# design.net
KiCad netlist of a schematic drawn in Altium Designer
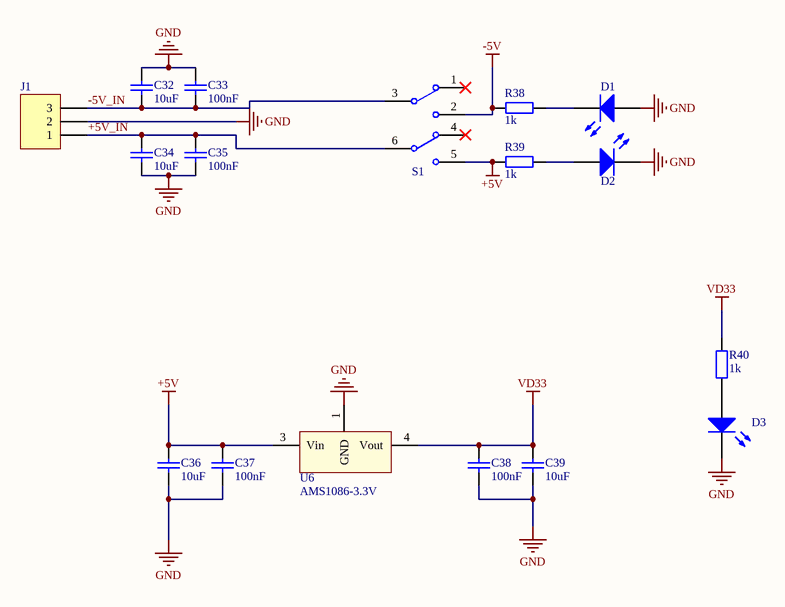
[diagram p0: 电源电路.SchDoc]

(export (version "E")
  (design (tool "Eeschema 10.0.6"))
  (components
    (comp (ref "C32")
      (value "10uF")
      (footprint "LC-0805_C")
      (description "100nF��0805��50V,+/-10%")
      (libsource (lib "ECG") (part "Cap"))
    )
    (comp (ref "C33")
      (value "100nF")
      (footprint "LC-0805_C")
      (description "100nF��0805��50V,+/-10%")
      (libsource (lib "ECG") (part "Cap"))
    )
    (comp (ref "C34")
      (value "10uF")
      (footprint "LC-0805_C")
      (description "100nF��0805��50V,+/-10%")
      (libsource (lib "ECG") (part "Cap"))
    )
    (comp (ref "C35")
      (value "100nF")
      (footprint "LC-0805_C")
      (description "100nF��0805��50V,+/-10%")
      (libsource (lib "ECG") (part "Cap"))
    )
    (comp (ref "C36")
      (value "10uF")
      (footprint "LC-0805_C")
      (description "100nF��0805��50V,+/-10%")
      (libsource (lib "ECG") (part "Cap"))
    )
    (comp (ref "C37")
      (value "100nF")
      (footprint "LC-0805_C")
      (description "100nF��0805��50V,+/-10%")
      (libsource (lib "ECG") (part "Cap"))
    )
    (comp (ref "C38")
      (value "100nF")
      (footprint "LC-0805_C")
      (description "100nF��0805��50V,+/-10%")
      (libsource (lib "ECG") (part "Cap"))
    )
    (comp (ref "C39")
      (value "10uF")
      (footprint "LC-0805_C")
      (description "100nF��0805��50V,+/-10%")
      (libsource (lib "ECG") (part "Cap"))
    )
    (comp (ref "D1")
      (value "LED0")
      (footprint "0805-POLAR")
      (description "��������ܣ�0805���׷��̹�")
      (fields (field (name "PUBLISHER") "Altium Limited"))
      (libsource (lib "ECG") (part "LED0"))
    )
    (comp (ref "D2")
      (value "LED0")
      (footprint "0805-POLAR")
      (description "��������ܣ�0805���׷��̹�")
      (fields (field (name "PUBLISHER") "Altium Limited"))
      (libsource (lib "ECG") (part "LED0"))
    )
    (comp (ref "D3")
      (value "LED0")
      (footprint "0805-POLAR")
      (description "��������ܣ�0805���׷��̹�")
      (fields (field (name "PUBLISHER") "Altium Limited"))
      (libsource (lib "ECG") (part "LED0"))
    )
    (comp (ref "J1")
      (value "������")
      (footprint "HDR1X3")
      (description "1*3Pin,2.54mm��൥����")
      (fields (field (name "PUBLISHER") "Altium Limited"))
      (libsource (lib "ECG") (part "Header 3"))
    )
    (comp (ref "R38")
      (value "1k")
      (footprint "LC-0805_R")
      (description "10k��,0805,��5%")
      (libsource (lib "ECG") (part "R"))
    )
    (comp (ref "R39")
      (value "1k")
      (footprint "LC-0805_R")
      (description "10k��,0805,��5%")
      (libsource (lib "ECG") (part "R"))
    )
    (comp (ref "R40")
      (value "1k")
      (footprint "LC-0805_R")
      (description "10k��,0805,��5%")
      (libsource (lib "ECG") (part "R"))
    )
    (comp (ref "S1")
      (value "��������")
      (footprint "DPDT-6")
      (description "8*8mm����˫·��������")
      (libsource (lib "ECG") (part "SW-6"))
    )
    (comp (ref "U6")
      (value "AMS1086-3.3V")
      (footprint "TO-252")
      (description "AMS1086-3.3V,TO252��װ")
      (libsource (lib "ECG") (part "AMS1086-3.3"))
    )
  )
  (nets
    (net (code "1") (name "+5V") (class "Default")
      (node (ref "C36") (pin "1") (pinfunction "1_1") (pintype "passive"))
      (node (ref "C37") (pin "1") (pinfunction "1_1") (pintype "passive"))
      (node (ref "R39") (pin "1") (pintype "passive"))
      (node (ref "S1") (pin "5") (pinfunction "5_5") (pintype "passive"))
      (node (ref "U6") (pin "3") (pinfunction "Vin_3") (pintype "passive"))
    )
    (net (code "2") (name "-5V") (class "Default")
      (node (ref "R38") (pin "1") (pintype "passive"))
      (node (ref "S1") (pin "2") (pinfunction "2_2") (pintype "passive"))
    )
    (net (code "3") (name "/+5V_IN") (class "Default")
      (node (ref "C34") (pin "1") (pinfunction "1_1") (pintype "passive"))
      (node (ref "C35") (pin "1") (pinfunction "1_1") (pintype "passive"))
      (node (ref "J1") (pin "1") (pinfunction "1_1") (pintype "passive"))
      (node (ref "S1") (pin "6") (pinfunction "6_6") (pintype "passive"))
    )
    (net (code "4") (name "/-5V_IN") (class "Default")
      (node (ref "C32") (pin "2") (pinfunction "2_2") (pintype "passive"))
      (node (ref "C33") (pin "2") (pinfunction "2_2") (pintype "passive"))
      (node (ref "J1") (pin "3") (pinfunction "3_3") (pintype "passive"))
      (node (ref "S1") (pin "3") (pinfunction "3_3") (pintype "passive"))
    )
    (net (code "5") (name "GND") (class "Default")
      (node (ref "C32") (pin "1") (pinfunction "1_1") (pintype "passive"))
      (node (ref "C33") (pin "1") (pinfunction "1_1") (pintype "passive"))
      (node (ref "C34") (pin "2") (pinfunction "2_2") (pintype "passive"))
      (node (ref "C35") (pin "2") (pinfunction "2_2") (pintype "passive"))
      (node (ref "C36") (pin "2") (pinfunction "2_2") (pintype "passive"))
      (node (ref "C37") (pin "2") (pinfunction "2_2") (pintype "passive"))
      (node (ref "C38") (pin "2") (pinfunction "2_2") (pintype "passive"))
      (node (ref "C39") (pin "2") (pinfunction "2_2") (pintype "passive"))
      (node (ref "D1") (pin "1") (pinfunction "A_1") (pintype "passive"))
      (node (ref "D2") (pin "2") (pinfunction "K_2") (pintype "passive"))
      (node (ref "D3") (pin "2") (pinfunction "K_2") (pintype "passive"))
      (node (ref "J1") (pin "2") (pinfunction "2_2") (pintype "passive"))
      (node (ref "U6") (pin "1") (pinfunction "GND_1") (pintype "passive"))
    )
    (net (code "6") (name "Net-(D1-K)") (class "Default")
      (node (ref "D1") (pin "2") (pinfunction "K_2") (pintype "passive"))
      (node (ref "R38") (pin "2") (pintype "passive"))
    )
    (net (code "7") (name "Net-(D2-A)") (class "Default")
      (node (ref "D2") (pin "1") (pinfunction "A_1") (pintype "passive"))
      (node (ref "R39") (pin "2") (pintype "passive"))
    )
    (net (code "8") (name "Net-(D3-A)") (class "Default")
      (node (ref "D3") (pin "1") (pinfunction "A_1") (pintype "passive"))
      (node (ref "R40") (pin "1") (pintype "passive"))
    )
    (net (code "9") (name "VD33") (class "Default")
      (node (ref "C38") (pin "1") (pinfunction "1_1") (pintype "passive"))
      (node (ref "C39") (pin "1") (pinfunction "1_1") (pintype "passive"))
      (node (ref "R40") (pin "2") (pintype "passive"))
      (node (ref "U6") (pin "4") (pinfunction "Vout_4") (pintype "passive"))
    )
    (net (code "10") (name "unconnected-(S1-Pad1)") (class "Default")
      (node (ref "S1") (pin "1") (pinfunction "1_1") (pintype "passive+no_connect"))
    )
    (net (code "11") (name "unconnected-(S1-Pad4)") (class "Default")
      (node (ref "S1") (pin "4") (pinfunction "4_4") (pintype "passive+no_connect"))
    )
  )
)
